# PowerSection.net
KiCad netlist of a schematic drawn in Altium Designer
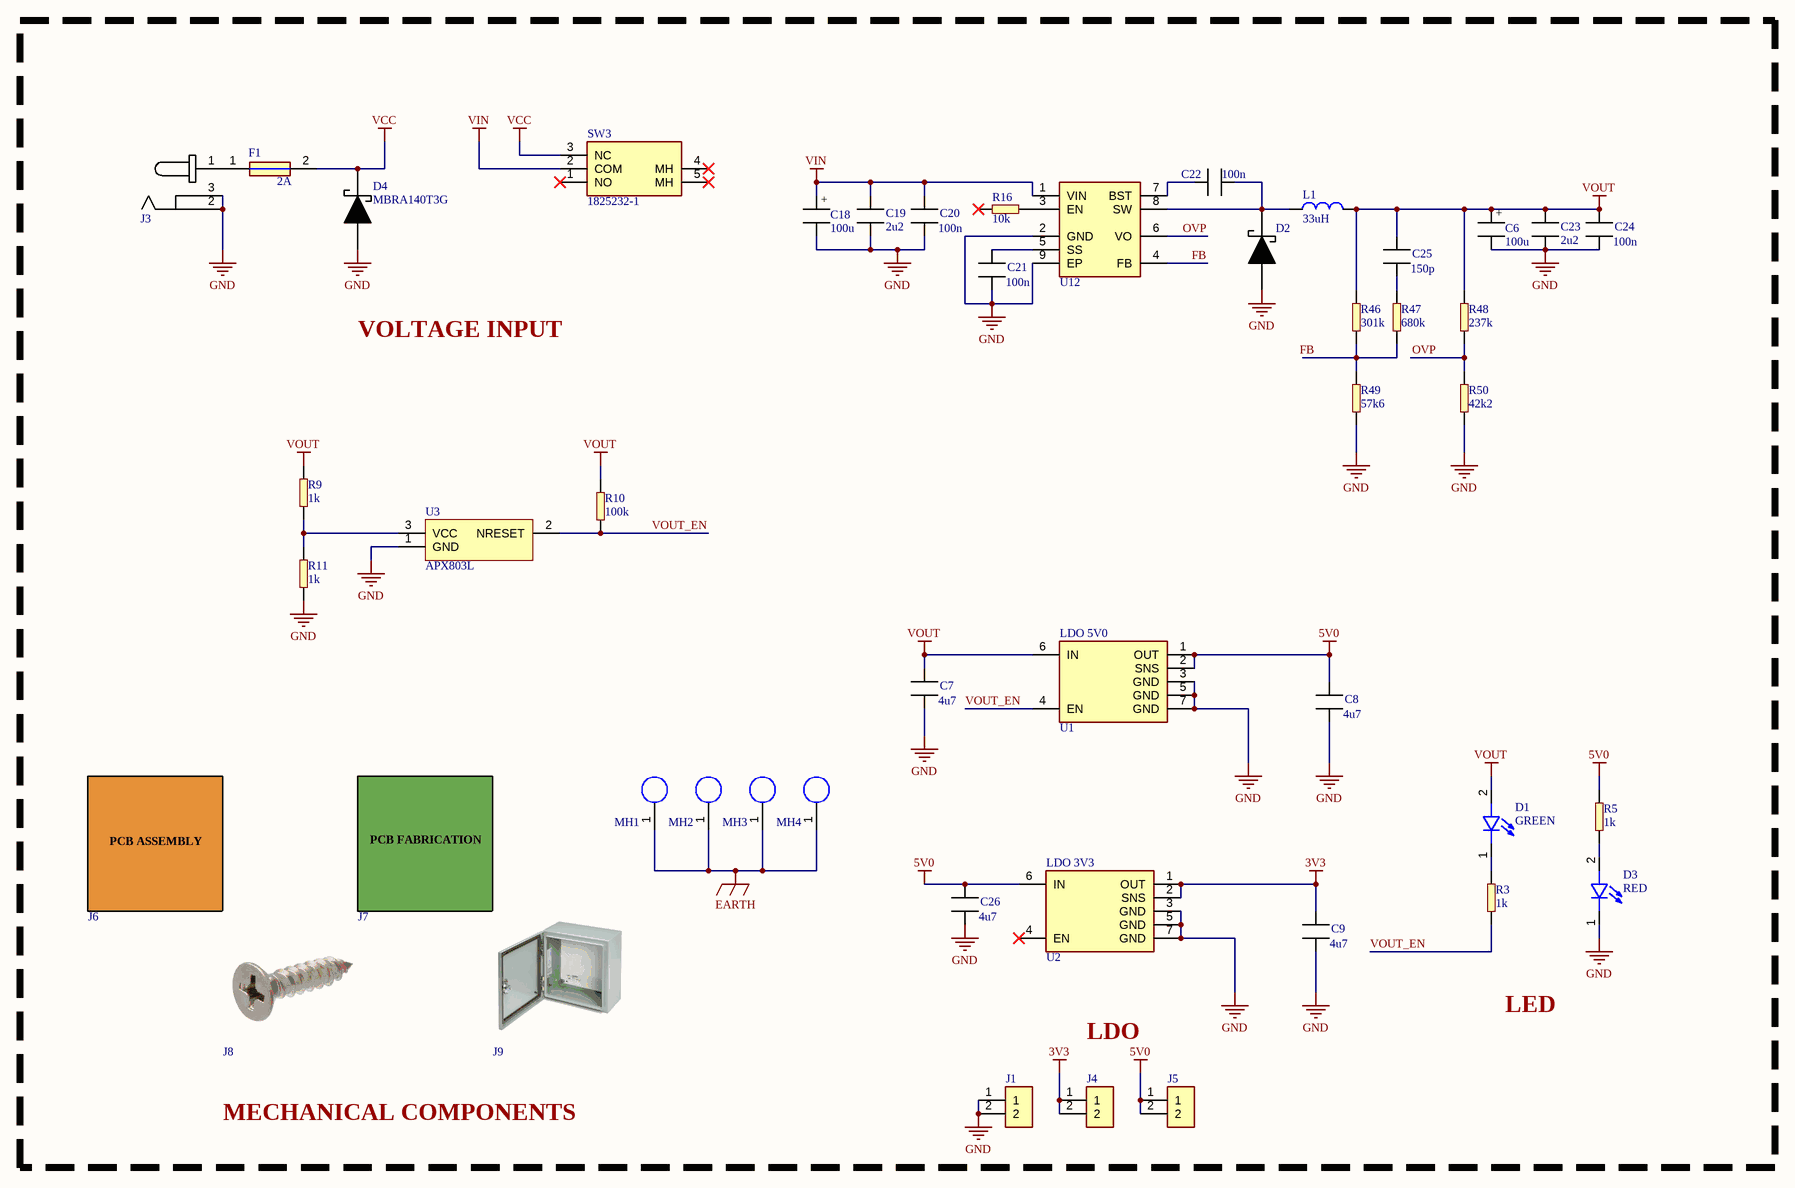
[diagram p0: PowerSection.SchDoc]

(export (version "E")
  (design (tool "Eeschema 10.0.6"))
  (components
    (comp (ref "C6")
      (value "100u")
      (footprint "CAP_12.5_14")
      (description "Electrolytic Capacitor SMD")
      (fields (field (name "Comment") "CAP_12.5_14"))
      (libsource (lib "ElectrolyticCapacitor") (part "CAP_12.5_14"))
    )
    (comp (ref "C7")
      (value "4u7")
      (footprint "CAPC1608X10N")
      (description "MLCC 0603")
      (fields (field (name "Comment") "ERP_102-1"))
      (libsource (lib "Capacitor") (part "MLCC_0603"))
    )
    (comp (ref "C8")
      (value "4u7")
      (footprint "CAPC1608X10N")
      (description "MLCC 0603")
      (fields (field (name "Comment") "ERP_102-1"))
      (libsource (lib "Capacitor") (part "MLCC_0603"))
    )
    (comp (ref "C9")
      (value "4u7")
      (footprint "CAPC1608X10N")
      (description "MLCC 0603")
      (fields (field (name "Comment") "ERP_102-1"))
      (libsource (lib "Capacitor") (part "MLCC_0603"))
    )
    (comp (ref "C18")
      (value "100u")
      (footprint "CAP_12.5_14")
      (description "Electrolytic Capacitor SMD")
      (fields (field (name "Comment") "CAP_12.5_14"))
      (libsource (lib "ElectrolyticCapacitor") (part "CAP_12.5_14"))
    )
    (comp (ref "C19")
      (value "2u2")
      (footprint "CAPC1608X10N")
      (description "MLCC 0603")
      (fields (field (name "Comment") "ERP_102-1"))
      (libsource (lib "Capacitor") (part "MLCC_0603"))
    )
    (comp (ref "C20")
      (value "100n")
      (footprint "CAPC1608X10N")
      (description "Chip Capacitor, 2-Leads, Body 1.60x0.80mm, IPC Medium Density")
      (fields (field (name "Comment") "ERP_102-1"))
      (libsource (lib "Capacitor") (part "MLCC_0603"))
    )
    (comp (ref "C21")
      (value "100n")
      (footprint "CAPC1608X10N")
      (description "Chip Capacitor, 2-Leads, Body 1.60x0.80mm, IPC Medium Density")
      (fields (field (name "Comment") "ERP_102-1"))
      (libsource (lib "Capacitor") (part "MLCC_0603"))
    )
    (comp (ref "C22")
      (value "100n")
      (footprint "CAPC1608X10N")
      (description "Chip Capacitor, 2-Leads, Body 1.60x0.80mm, IPC Medium Density")
      (fields (field (name "Comment") "ERP_102-1"))
      (libsource (lib "Capacitor") (part "MLCC_0603"))
    )
    (comp (ref "C23")
      (value "2u2")
      (footprint "CAPC1608X10N")
      (description "MLCC 0603")
      (fields (field (name "Comment") "ERP_102-1"))
      (libsource (lib "Capacitor") (part "MLCC_0603"))
    )
    (comp (ref "C24")
      (value "100n")
      (footprint "CAPC1608X10N")
      (description "Chip Capacitor, 2-Leads, Body 1.60x0.80mm, IPC Medium Density")
      (fields (field (name "Comment") "ERP_102-1"))
      (libsource (lib "Capacitor") (part "MLCC_0603"))
    )
    (comp (ref "C25")
      (value "150p")
      (footprint "CAPC1608X10N")
      (description "Chip Capacitor, 2-Leads, Body 1.60x0.80mm, IPC Medium Density")
      (fields (field (name "Comment") "ERP_102-1"))
      (libsource (lib "Capacitor") (part "MLCC_0603"))
    )
    (comp (ref "C26")
      (value "4u7")
      (footprint "CAPC1608X10N")
      (description "MLCC 0603")
      (fields (field (name "Comment") "ERP_102-1"))
      (libsource (lib "Capacitor") (part "MLCC_0603"))
    )
    (comp (ref "D1")
      (value "GREEN")
      (footprint "LED_2SMD")
      (description "LED GREEN CLEAR 1204 SMD R/A")
      (fields (field (name "Comment") "LED_2SMD"))
      (libsource (lib "LED") (part "LED_2SMD"))
    )
    (comp (ref "D2")
      (value "ERP_104-3")
      (footprint "B560C-13-F")
      (libsource (lib "Schottky") (part "B560C-13-F"))
    )
    (comp (ref "D3")
      (value "RED")
      (footprint "LED_2SMD")
      (description "LED RED CLEAR 1204 SMD R/A")
      (fields (field (name "Comment") "LED_2SMD"))
      (libsource (lib "LED") (part "LED_2SMD"))
    )
    (comp (ref "D4")
      (value "MBRA140T3G")
      (footprint "SS14_SMA")
      (description "SS14_SMA")
      (fields (field (name "Comment") "ERP_104-3"))
      (libsource (lib "Schottky") (part "SS14_SMA"))
    )
    (comp (ref "F1")
      (value "2A")
      (footprint "0679L")
      (description "FUSE BRD MNT 2SMD")
      (fields (field (name "Comment") "0679L"))
      (libsource (lib "BlowFuse") (part "0679L"))
    )
    (comp (ref "J1")
      (value "ERP_148-2")
      (footprint "2PX1R")
      (description "2PX1R")
      (libsource (lib "Male_Header_P2.54") (part "2PX1R"))
    )
    (comp (ref "J3")
      (value "KLDX-0202-AC")
      (footprint "KLDX-0202-AC")
      (description "CONN PWR JACK 2X5.5MM KINKED PIN")
      (libsource (lib "Connectors") (part "KLDX-0202-AC"))
    )
    (comp (ref "J4")
      (value "ERP_148-2")
      (footprint "2PX1R")
      (description "2PX1R")
      (libsource (lib "Male_Header_P2.54") (part "2PX1R"))
    )
    (comp (ref "J5")
      (value "ERP_148-2")
      (footprint "2PX1R")
      (description "2PX1R")
      (libsource (lib "Male_Header_P2.54") (part "2PX1R"))
    )
    (comp (ref "J9")
      (value "ENCLOSURE")
      (description "PCB Enclosure")
      (libsource (lib "Jumper") (part "ENCLOSURE"))
    )
    (comp (ref "L1")
      (value "33uH")
      (footprint "IND_1212")
      (description "IND_1212")
      (fields (field (name "Comment") "ERP_103-3"))
      (libsource (lib "Inductor") (part "IND_1212"))
    )
    (comp (ref "MH1")
      (value "MountingHole4X6")
      (footprint "MountingHole4X6")
      (libsource (lib "Jumper") (part "MountingHole4X6"))
    )
    (comp (ref "MH2")
      (value "MountingHole4X6")
      (footprint "MountingHole4X6")
      (libsource (lib "Jumper") (part "MountingHole4X6"))
    )
    (comp (ref "MH3")
      (value "MountingHole4X6")
      (footprint "MountingHole4X6")
      (libsource (lib "Jumper") (part "MountingHole4X6"))
    )
    (comp (ref "MH4")
      (value "MountingHole4X6")
      (footprint "MountingHole4X6")
      (libsource (lib "Jumper") (part "MountingHole4X6"))
    )
    (comp (ref "R3")
      (value "1k")
      (footprint "RES_0603")
      (description "RES_0603")
      (fields (field (name "Comment") "ERP_101-1"))
      (libsource (lib "") (part "RES_0603_1"))
    )
    (comp (ref "R5")
      (value "1k")
      (footprint "RES_0603")
      (description "RES_0603")
      (fields (field (name "Comment") "ERP_101-1"))
      (libsource (lib "Resistor") (part "RES_0603"))
    )
    (comp (ref "R9")
      (value "1k")
      (footprint "RES_0603")
      (description "RES_0603")
      (fields (field (name "Comment") "ERP_101-1"))
      (libsource (lib "") (part "RES_0603_1"))
    )
    (comp (ref "R10")
      (value "100k")
      (footprint "RES_0603")
      (description "RES_0603")
      (fields (field (name "Comment") "ERP_101-1"))
      (libsource (lib "") (part "RES_0603_1"))
    )
    (comp (ref "R11")
      (value "1k")
      (footprint "RES_0603")
      (description "RES_0603")
      (fields (field (name "Comment") "ERP_101-1"))
      (libsource (lib "") (part "RES_0603_1"))
    )
    (comp (ref "R16")
      (value "10k")
      (footprint "RES_0603")
      (description "RES_0603")
      (fields (field (name "Comment") "ERP_101-1"))
      (libsource (lib "") (part "RES_0603_2"))
    )
    (comp (ref "R46")
      (value "301k")
      (footprint "RES_0603")
      (description "RES_0603")
      (fields (field (name "Comment") "ERP_101-1"))
      (libsource (lib "") (part "RES_0603_1"))
    )
    (comp (ref "R47")
      (value "680k")
      (footprint "RES_0603")
      (description "RES_0603")
      (fields (field (name "Comment") "ERP_101-1"))
      (libsource (lib "") (part "RES_0603_1"))
    )
    (comp (ref "R48")
      (value "237k")
      (footprint "RES_0603")
      (description "RES_0603")
      (fields (field (name "Comment") "ERP_101-1"))
      (libsource (lib "") (part "RES_0603_1"))
    )
    (comp (ref "R49")
      (value "57k6")
      (footprint "RES_0603")
      (description "RES_0603")
      (fields (field (name "Comment") "ERP_101-1"))
      (libsource (lib "") (part "RES_0603_1"))
    )
    (comp (ref "R50")
      (value "42k2")
      (footprint "RES_0603")
      (description "RES_0603")
      (fields (field (name "Comment") "ERP_101-1"))
      (libsource (lib "") (part "RES_0603_1"))
    )
    (comp (ref "SW3")
      (value "1825232-1")
      (footprint "3PIN_SPDT_TH_RA")
      (fields (field (name "Comment") "ERP_110-4"))
      (libsource (lib "Switch") (part "3PIN_SPDT_TH_RA"))
    )
    (comp (ref "U1")
      (value "LDO 5V0")
      (footprint "TLV767XXDRV")
      (description "IC REG LINEAR")
      (fields (field (name "Comment") "TLV767XXDRV"))
      (libsource (lib "VoltageRegulator") (part "TLV767XXDRV"))
    )
    (comp (ref "U2")
      (value "LDO 3V3")
      (footprint "TLV767XXDRV")
      (description "IC REG LINEAR")
      (fields (field (name "Comment") "TLV767XXDRV"))
      (libsource (lib "VoltageRegulator") (part "TLV767XXDRV"))
    )
    (comp (ref "U3")
      (value "APX803L")
      (footprint "APX803L")
      (description "IC SUPERVISOR 1 CHANNEL SOT23")
      (libsource (lib "VoltageDetector") (part "APX803L"))
    )
    (comp (ref "U12")
      (value "MP24943DN")
      (footprint "MP24943DN")
      (description "IC REG BUCK ADJ 3A 8SOIC")
      (libsource (lib "DCDC_Switcher") (part "MP24943DN"))
    )
  )
  (nets
    (net (code "1") (name "/FB") (class "Default")
      (node (ref "R46") (pin "1") (pinfunction "1_1") (pintype "passive"))
      (node (ref "R47") (pin "1") (pinfunction "1_1") (pintype "passive"))
      (node (ref "R49") (pin "2") (pinfunction "2_2") (pintype "passive"))
      (node (ref "U12") (pin "4") (pinfunction "FB_4") (pintype "passive"))
    )
    (net (code "2") (name "/OVP") (class "Default")
      (node (ref "R48") (pin "1") (pinfunction "1_1") (pintype "passive"))
      (node (ref "R50") (pin "2") (pinfunction "2_2") (pintype "passive"))
      (node (ref "U12") (pin "6") (pinfunction "VO_6") (pintype "passive"))
    )
    (net (code "3") (name "/VOUT_EN") (class "Default")
      (node (ref "R10") (pin "1") (pinfunction "1_1") (pintype "passive"))
      (node (ref "R3") (pin "1") (pinfunction "1_1") (pintype "passive"))
      (node (ref "U1") (pin "4") (pinfunction "EN_4") (pintype "passive"))
      (node (ref "U3") (pin "2") (pinfunction "NRESET_2") (pintype "passive"))
    )
    (net (code "4") (name "3V3") (class "Default")
      (node (ref "C9") (pin "1") (pinfunction "1_1") (pintype "passive"))
      (node (ref "J4") (pin "1") (pinfunction "1_1") (pintype "passive"))
      (node (ref "J4") (pin "2") (pinfunction "2_2") (pintype "passive"))
      (node (ref "U2") (pin "1") (pinfunction "OUT_1") (pintype "passive"))
      (node (ref "U2") (pin "2") (pinfunction "SNS_2") (pintype "passive"))
    )
    (net (code "5") (name "5V0") (class "Default")
      (node (ref "C26") (pin "1") (pinfunction "1_1") (pintype "passive"))
      (node (ref "C8") (pin "1") (pinfunction "1_1") (pintype "passive"))
      (node (ref "J5") (pin "1") (pinfunction "1_1") (pintype "passive"))
      (node (ref "J5") (pin "2") (pinfunction "2_2") (pintype "passive"))
      (node (ref "R5") (pin "1") (pinfunction "1_1") (pintype "passive"))
      (node (ref "U1") (pin "1") (pinfunction "OUT_1") (pintype "passive"))
      (node (ref "U1") (pin "2") (pinfunction "SNS_2") (pintype "passive"))
      (node (ref "U2") (pin "6") (pinfunction "IN_6") (pintype "passive"))
    )
    (net (code "6") (name "EARTH") (class "Default")
      (node (ref "MH1") (pin "1") (pinfunction "1_1") (pintype "passive"))
      (node (ref "MH2") (pin "1") (pinfunction "1_1") (pintype "passive"))
      (node (ref "MH3") (pin "1") (pinfunction "1_1") (pintype "passive"))
      (node (ref "MH4") (pin "1") (pinfunction "1_1") (pintype "passive"))
    )
    (net (code "7") (name "GND") (class "Default")
      (node (ref "C18") (pin "2") (pinfunction "2_2") (pintype "passive"))
      (node (ref "C19") (pin "1") (pinfunction "1_1") (pintype "passive"))
      (node (ref "C20") (pin "2") (pinfunction "2_2") (pintype "passive"))
      (node (ref "C21") (pin "2") (pinfunction "2_2") (pintype "passive"))
      (node (ref "C23") (pin "1") (pinfunction "1_1") (pintype "passive"))
      (node (ref "C24") (pin "2") (pinfunction "2_2") (pintype "passive"))
      (node (ref "C26") (pin "2") (pinfunction "2_2") (pintype "passive"))
      (node (ref "C6") (pin "2") (pinfunction "2_2") (pintype "passive"))
      (node (ref "C7") (pin "2") (pinfunction "2_2") (pintype "passive"))
      (node (ref "C8") (pin "2") (pinfunction "2_2") (pintype "passive"))
      (node (ref "C9") (pin "2") (pinfunction "2_2") (pintype "passive"))
      (node (ref "D2") (pin "2") (pinfunction "A_2") (pintype "passive"))
      (node (ref "D3") (pin "1") (pinfunction "1_1") (pintype "passive"))
      (node (ref "D4") (pin "2") (pinfunction "A_2") (pintype "passive"))
      (node (ref "J1") (pin "1") (pinfunction "1_1") (pintype "passive"))
      (node (ref "J1") (pin "2") (pinfunction "2_2") (pintype "passive"))
      (node (ref "J3") (pin "2") (pinfunction "2_2") (pintype "passive"))
      (node (ref "J3") (pin "3") (pinfunction "3_3") (pintype "passive"))
      (node (ref "R11") (pin "1") (pinfunction "1_1") (pintype "passive"))
      (node (ref "R49") (pin "1") (pinfunction "1_1") (pintype "passive"))
      (node (ref "R50") (pin "1") (pinfunction "1_1") (pintype "passive"))
      (node (ref "U1") (pin "3") (pinfunction "GND_3") (pintype "passive"))
      (node (ref "U1") (pin "5") (pinfunction "GND_5") (pintype "passive"))
      (node (ref "U1") (pin "7") (pinfunction "GND_7") (pintype "passive"))
      (node (ref "U12") (pin "2") (pinfunction "GND_2") (pintype "passive"))
      (node (ref "U12") (pin "9") (pinfunction "EP_9") (pintype "passive"))
      (node (ref "U2") (pin "3") (pinfunction "GND_3") (pintype "passive"))
      (node (ref "U2") (pin "5") (pinfunction "GND_5") (pintype "passive"))
      (node (ref "U2") (pin "7") (pinfunction "GND_7") (pintype "passive"))
      (node (ref "U3") (pin "1") (pinfunction "GND_1") (pintype "passive"))
    )
    (net (code "8") (name "Net-(C25-Pad2)") (class "Default")
      (node (ref "C25") (pin "2") (pinfunction "2_2") (pintype "passive"))
      (node (ref "R47") (pin "2") (pinfunction "2_2") (pintype "passive"))
    )
    (net (code "9") (name "Net-(D1-Pad1)") (class "Default")
      (node (ref "D1") (pin "1") (pinfunction "1_1") (pintype "passive"))
      (node (ref "R3") (pin "2") (pinfunction "2_2") (pintype "passive"))
    )
    (net (code "10") (name "Net-(D2-C)") (class "Default")
      (node (ref "C22") (pin "2") (pinfunction "2_2") (pintype "passive"))
      (node (ref "D2") (pin "1") (pinfunction "C_1") (pintype "passive"))
      (node (ref "L1") (pin "1") (pinfunction "1_1") (pintype "passive"))
      (node (ref "U12") (pin "8") (pinfunction "SW_8") (pintype "passive"))
    )
    (net (code "11") (name "Net-(D3-Pad2)") (class "Default")
      (node (ref "D3") (pin "2") (pinfunction "2_2") (pintype "passive"))
      (node (ref "R5") (pin "2") (pinfunction "2_2") (pintype "passive"))
    )
    (net (code "12") (name "Net-(F1-Pad1)") (class "Default")
      (node (ref "F1") (pin "1") (pinfunction "1_1") (pintype "passive"))
      (node (ref "J3") (pin "1") (pinfunction "1_1") (pintype "passive"))
    )
    (net (code "13") (name "Net-(U3-VCC)") (class "Default")
      (node (ref "R11") (pin "2") (pinfunction "2_2") (pintype "passive"))
      (node (ref "R9") (pin "1") (pinfunction "1_1") (pintype "passive"))
      (node (ref "U3") (pin "3") (pinfunction "VCC_3") (pintype "passive"))
    )
    (net (code "14") (name "Net-(U12-BST)") (class "Default")
      (node (ref "C22") (pin "1") (pinfunction "1_1") (pintype "passive"))
      (node (ref "U12") (pin "7") (pinfunction "BST_7") (pintype "passive"))
    )
    (net (code "15") (name "Net-(U12-EN)") (class "Default")
      (node (ref "R16") (pin "1") (pinfunction "1_1") (pintype "passive"))
      (node (ref "U12") (pin "3") (pinfunction "EN_3") (pintype "passive"))
    )
    (net (code "16") (name "Net-(U12-SS)") (class "Default")
      (node (ref "C21") (pin "1") (pinfunction "1_1") (pintype "passive"))
      (node (ref "U12") (pin "5") (pinfunction "SS_5") (pintype "passive"))
    )
    (net (code "17") (name "VCC") (class "Default")
      (node (ref "D4") (pin "1") (pinfunction "C_1") (pintype "passive"))
      (node (ref "F1") (pin "2") (pinfunction "2_2") (pintype "passive"))
      (node (ref "SW3") (pin "3") (pinfunction "NC_3") (pintype "passive"))
    )
    (net (code "18") (name "VIN") (class "Default")
      (node (ref "C18") (pin "1") (pinfunction "1_1") (pintype "passive"))
      (node (ref "C19") (pin "2") (pinfunction "2_2") (pintype "passive"))
      (node (ref "C20") (pin "1") (pinfunction "1_1") (pintype "passive"))
      (node (ref "SW3") (pin "2") (pinfunction "COM_2") (pintype "passive"))
      (node (ref "U12") (pin "1") (pinfunction "VIN_1") (pintype "passive"))
    )
    (net (code "19") (name "VOUT") (class "Default")
      (node (ref "C23") (pin "2") (pinfunction "2_2") (pintype "passive"))
      (node (ref "C24") (pin "1") (pinfunction "1_1") (pintype "passive"))
      (node (ref "C25") (pin "1") (pinfunction "1_1") (pintype "passive"))
      (node (ref "C6") (pin "1") (pinfunction "1_1") (pintype "passive"))
      (node (ref "C7") (pin "1") (pinfunction "1_1") (pintype "passive"))
      (node (ref "D1") (pin "2") (pinfunction "2_2") (pintype "passive"))
      (node (ref "L1") (pin "2") (pinfunction "2_2") (pintype "passive"))
      (node (ref "R10") (pin "2") (pinfunction "2_2") (pintype "passive"))
      (node (ref "R46") (pin "2") (pinfunction "2_2") (pintype "passive"))
      (node (ref "R48") (pin "2") (pinfunction "2_2") (pintype "passive"))
      (node (ref "R9") (pin "2") (pinfunction "2_2") (pintype "passive"))
      (node (ref "U1") (pin "6") (pinfunction "IN_6") (pintype "passive"))
    )
    (net (code "20") (name "unconnected-(R16-Pad2)") (class "Default")
      (node (ref "R16") (pin "2") (pinfunction "2_2") (pintype "passive+no_connect"))
    )
    (net (code "21") (name "unconnected-(SW3-MH-Pad4)") (class "Default")
      (node (ref "SW3") (pin "4") (pinfunction "MH_4") (pintype "passive+no_connect"))
    )
    (net (code "22") (name "unconnected-(SW3-MH-Pad5)") (class "Default")
      (node (ref "SW3") (pin "5") (pinfunction "MH_5") (pintype "passive+no_connect"))
    )
    (net (code "23") (name "unconnected-(SW3-NO-Pad1)") (class "Default")
      (node (ref "SW3") (pin "1") (pinfunction "NO_1") (pintype "passive+no_connect"))
    )
    (net (code "24") (name "unconnected-(U2-EN-Pad4)") (class "Default")
      (node (ref "U2") (pin "4") (pinfunction "EN_4") (pintype "passive+no_connect"))
    )
  )
)
